# project1.net
KiCad netlist of a schematic drawn in EAGLE
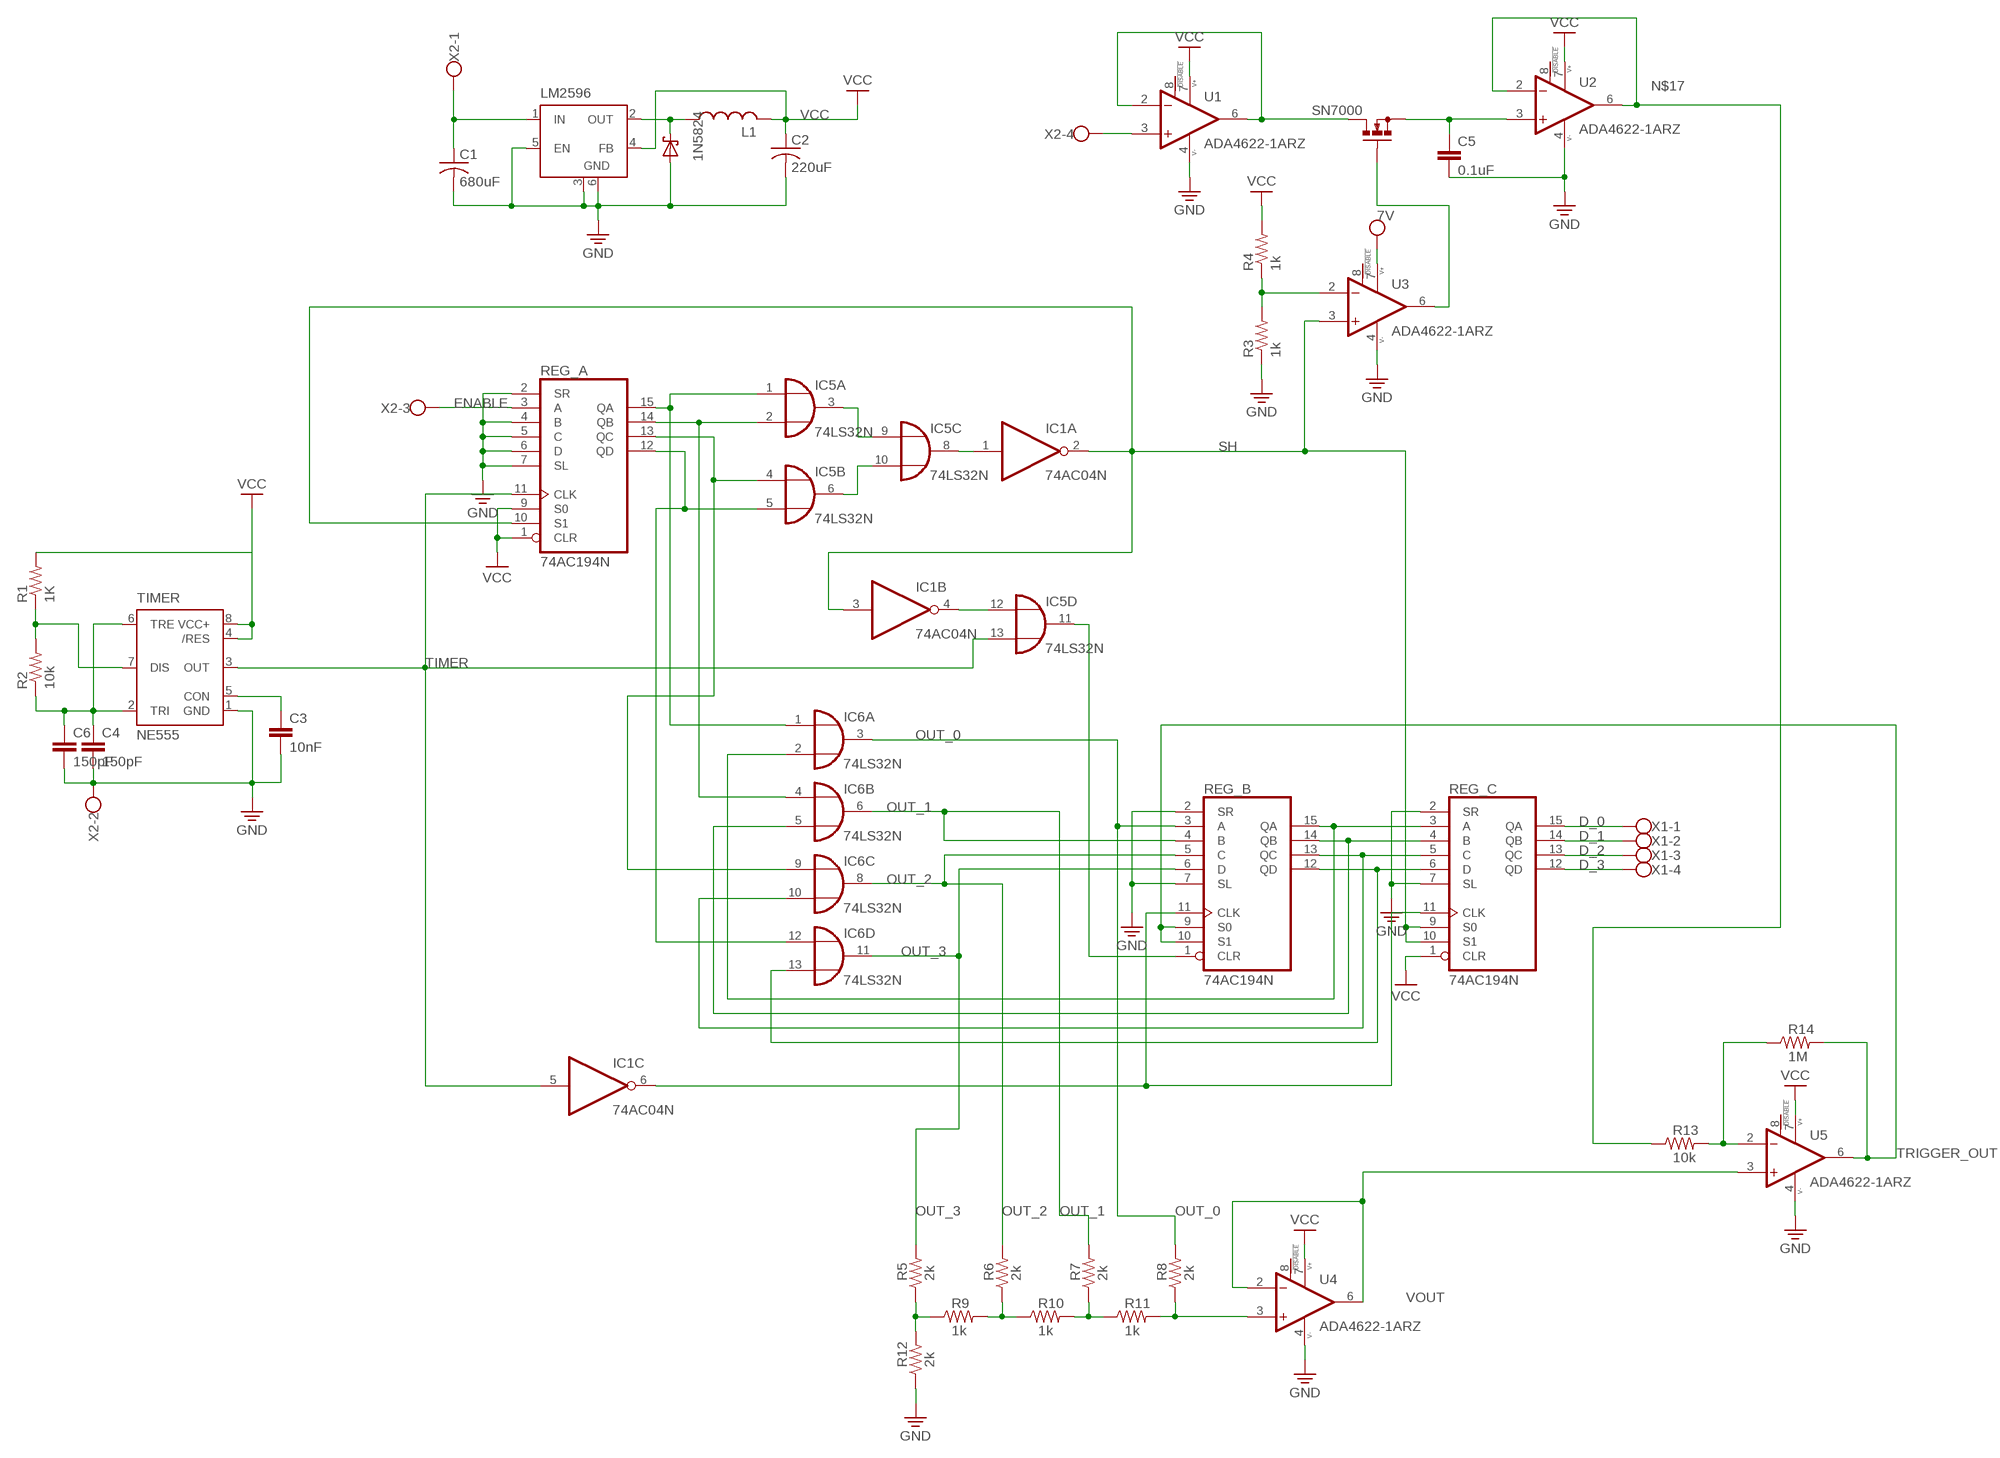
[diagram p0: schematic, sheet 1]

(export (version "E")
  (design (tool "Eeschema 10.0.6"))
  (components
    (comp (ref "1N5824")
      (value "SCHOTTKY-DIODECB417-15")
      (footprint "eagle-import:CB417-15")
      (libsource (lib "eagle-import") (part "SCHOTTKY-DIODECB417-15"))
    )
    (comp (ref "C1")
      (value "680uF")
      (footprint "eagle-import:C025-024X044")
      (libsource (lib "eagle-import") (part "C-US025-024X044"))
    )
    (comp (ref "C2")
      (value "220uF")
      (footprint "eagle-import:C025-024X044")
      (libsource (lib "eagle-import") (part "C-US025-024X044"))
    )
    (comp (ref "C3")
      (value "10nF")
      (footprint "eagle-import:C050-024X044")
      (libsource (lib "eagle-import") (part "C-EU050-024X044"))
    )
    (comp (ref "C4")
      (value "150pF")
      (footprint "eagle-import:C050-024X044")
      (libsource (lib "eagle-import") (part "C-EU050-024X044"))
    )
    (comp (ref "C5")
      (value "0.1uF")
      (footprint "eagle-import:C050-024X044")
      (libsource (lib "eagle-import") (part "C-EU050-024X044"))
    )
    (comp (ref "C6")
      (value "150pF")
      (footprint "eagle-import:C050-024X044")
      (libsource (lib "eagle-import") (part "C-EU050-024X044"))
    )
    (comp (ref "IC1")
      (value "74AC04N")
      (footprint "eagle-import:DIL14")
      (libsource (lib "eagle-import") (part "7404NAC"))
    )
    (comp (ref "IC5")
      (value "74LS32N")
      (footprint "eagle-import:DIL14")
      (libsource (lib "eagle-import") (part "7432NLS"))
    )
    (comp (ref "IC6")
      (value "74LS32N")
      (footprint "eagle-import:DIL14")
      (libsource (lib "eagle-import") (part "7432NLS"))
    )
    (comp (ref "L1")
      (value "L-US0204/7")
      (footprint "eagle-import:0204_7")
      (libsource (lib "eagle-import") (part "L-US0204/7"))
    )
    (comp (ref "LM2596")
      (value "LM2596S")
      (footprint "eagle-import:TO263-5")
      (libsource (lib "eagle-import") (part "LM2596S"))
    )
    (comp (ref "R1")
      (value "1K")
      (footprint "eagle-import:0204_7")
      (libsource (lib "eagle-import") (part "R-US_0204/7"))
    )
    (comp (ref "R2")
      (value "10k")
      (footprint "eagle-import:0204_7")
      (libsource (lib "eagle-import") (part "R-US_0204/7"))
    )
    (comp (ref "R3")
      (value "1k")
      (footprint "eagle-import:0204_7")
      (libsource (lib "eagle-import") (part "R-US_0204/7"))
    )
    (comp (ref "R4")
      (value "1k")
      (footprint "eagle-import:0204_7")
      (libsource (lib "eagle-import") (part "R-US_0204/7"))
    )
    (comp (ref "R5")
      (value "2k")
      (footprint "eagle-import:0204_7")
      (libsource (lib "eagle-import") (part "R-US_0204/7"))
    )
    (comp (ref "R6")
      (value "2k")
      (footprint "eagle-import:0204_7")
      (libsource (lib "eagle-import") (part "R-US_0204/7"))
    )
    (comp (ref "R7")
      (value "2k")
      (footprint "eagle-import:0204_7")
      (libsource (lib "eagle-import") (part "R-US_0204/7"))
    )
    (comp (ref "R8")
      (value "2k")
      (footprint "eagle-import:0204_7")
      (libsource (lib "eagle-import") (part "R-US_0204/7"))
    )
    (comp (ref "R9")
      (value "1k")
      (footprint "eagle-import:0204_7")
      (libsource (lib "eagle-import") (part "R-US_0204/7"))
    )
    (comp (ref "R10")
      (value "1k")
      (footprint "eagle-import:0204_7")
      (libsource (lib "eagle-import") (part "R-US_0204/7"))
    )
    (comp (ref "R11")
      (value "1k")
      (footprint "eagle-import:0204_7")
      (libsource (lib "eagle-import") (part "R-US_0204/7"))
    )
    (comp (ref "R12")
      (value "2k")
      (footprint "eagle-import:0204_7")
      (libsource (lib "eagle-import") (part "R-US_0204/7"))
    )
    (comp (ref "R13")
      (value "10k")
      (footprint "eagle-import:0204_7")
      (libsource (lib "eagle-import") (part "R-US_0204/7"))
    )
    (comp (ref "R14")
      (value "1M")
      (footprint "eagle-import:0204_7")
      (libsource (lib "eagle-import") (part "R-US_0204/7"))
    )
    (comp (ref "REG_A")
      (value "74AC194N")
      (footprint "eagle-import:DIL16")
      (libsource (lib "eagle-import") (part "74194NAC"))
    )
    (comp (ref "REG_B")
      (value "74AC194N")
      (footprint "eagle-import:DIL16")
      (libsource (lib "eagle-import") (part "74194NAC"))
    )
    (comp (ref "REG_C")
      (value "74AC194N")
      (footprint "eagle-import:DIL16")
      (libsource (lib "eagle-import") (part "74194NAC"))
    )
    (comp (ref "SN7000")
      (value "BS170")
      (footprint "eagle-import:SOT54E")
      (libsource (lib "eagle-import") (part "BS170"))
    )
    (comp (ref "TIMER")
      (value "NE555")
      (footprint "eagle-import:DIL-08")
      (fields (field (name "MF") "Arrow Electronics") (field (name "MPN") "NE555N"))
      (libsource (lib "eagle-import") (part "NE555"))
    )
    (comp (ref "U1")
      (value "ADA4622-1ARZ")
      (footprint "eagle-import:SOIC127P600X175-8N")
      (fields (field (name "MF") "Analog Devices"))
      (libsource (lib "eagle-import") (part "ADA4622-1ARZ"))
    )
    (comp (ref "U2")
      (value "ADA4622-1ARZ")
      (footprint "eagle-import:SOIC127P600X175-8N")
      (fields (field (name "MF") "Analog Devices"))
      (libsource (lib "eagle-import") (part "ADA4622-1ARZ"))
    )
    (comp (ref "U3")
      (value "ADA4622-1ARZ")
      (footprint "eagle-import:SOIC127P600X175-8N")
      (fields (field (name "MF") "Analog Devices"))
      (libsource (lib "eagle-import") (part "ADA4622-1ARZ"))
    )
    (comp (ref "U4")
      (value "ADA4622-1ARZ")
      (footprint "eagle-import:SOIC127P600X175-8N")
      (fields (field (name "MF") "Analog Devices"))
      (libsource (lib "eagle-import") (part "ADA4622-1ARZ"))
    )
    (comp (ref "U5")
      (value "ADA4622-1ARZ")
      (footprint "eagle-import:SOIC127P600X175-8N")
      (fields (field (name "MF") "Analog Devices"))
      (libsource (lib "eagle-import") (part "ADA4622-1ARZ"))
    )
    (comp (ref "X1")
      (value "W237-4")
      (footprint "eagle-import:W237-4")
      (libsource (lib "eagle-import") (part "W237-4"))
    )
    (comp (ref "X2")
      (value "W237-4")
      (footprint "eagle-import:W237-4")
      (libsource (lib "eagle-import") (part "W237-4"))
    )
  )
  (nets
    (net (code "1") (name "/D_0") (class "Default")
      (node (ref "REG_C") (pin "15") (pinfunction "QA_15") (pintype "output"))
      (node (ref "X1") (pin "1") (pinfunction "KL_1") (pintype "passive"))
    )
    (net (code "2") (name "/D_1") (class "Default")
      (node (ref "REG_C") (pin "14") (pinfunction "QB_14") (pintype "output"))
      (node (ref "X1") (pin "2") (pinfunction "KL_2") (pintype "passive"))
    )
    (net (code "3") (name "/D_2") (class "Default")
      (node (ref "REG_C") (pin "13") (pinfunction "QC_13") (pintype "output"))
      (node (ref "X1") (pin "3") (pinfunction "KL_3") (pintype "passive"))
    )
    (net (code "4") (name "/D_3") (class "Default")
      (node (ref "REG_C") (pin "12") (pinfunction "QD_12") (pintype "output"))
      (node (ref "X1") (pin "4") (pinfunction "KL_4") (pintype "passive"))
    )
    (net (code "5") (name "/ENABLE") (class "Default")
      (node (ref "REG_A") (pin "3") (pinfunction "A_3") (pintype "input"))
      (node (ref "X2") (pin "3") (pinfunction "KL_3") (pintype "passive"))
    )
    (net (code "6") (name "/N$17") (class "Default")
      (node (ref "R13") (pin "1") (pinfunction "1_1") (pintype "passive"))
      (node (ref "U2") (pin "2") (pinfunction "-IN_2") (pintype "input"))
      (node (ref "U2") (pin "6") (pinfunction "OUT_6") (pintype "output"))
    )
    (net (code "7") (name "/OUT_0") (class "Default")
      (node (ref "IC6") (pin "3") (pinfunction "O_3") (pintype "output"))
      (node (ref "R8") (pin "2") (pinfunction "2_2") (pintype "passive"))
      (node (ref "REG_B") (pin "3") (pinfunction "A_3") (pintype "input"))
    )
    (net (code "8") (name "/OUT_1") (class "Default")
      (node (ref "IC6") (pin "6") (pinfunction "O_6") (pintype "output"))
      (node (ref "R7") (pin "2") (pinfunction "2_2") (pintype "passive"))
      (node (ref "REG_B") (pin "4") (pinfunction "B_4") (pintype "input"))
    )
    (net (code "9") (name "/OUT_2") (class "Default")
      (node (ref "IC6") (pin "8") (pinfunction "O_8") (pintype "output"))
      (node (ref "R6") (pin "2") (pinfunction "2_2") (pintype "passive"))
      (node (ref "REG_B") (pin "5") (pinfunction "C_5") (pintype "input"))
    )
    (net (code "10") (name "/OUT_3") (class "Default")
      (node (ref "IC6") (pin "11") (pinfunction "O_11") (pintype "output"))
      (node (ref "R5") (pin "2") (pinfunction "2_2") (pintype "passive"))
      (node (ref "REG_B") (pin "6") (pinfunction "D_6") (pintype "input"))
    )
    (net (code "11") (name "/SH") (class "Default")
      (node (ref "IC1") (pin "2") (pinfunction "O_2") (pintype "output"))
      (node (ref "IC1") (pin "3") (pinfunction "I_3") (pintype "input"))
      (node (ref "REG_A") (pin "10") (pinfunction "S1_10") (pintype "input"))
      (node (ref "REG_C") (pin "10") (pinfunction "S1_10") (pintype "input"))
      (node (ref "REG_C") (pin "9") (pinfunction "S0_9") (pintype "input"))
      (node (ref "U3") (pin "3") (pinfunction "+IN_3") (pintype "input"))
    )
    (net (code "12") (name "/TIMER") (class "Default")
      (node (ref "IC1") (pin "5") (pinfunction "I_5") (pintype "input"))
      (node (ref "IC5") (pin "13") (pinfunction "I1_13") (pintype "input"))
      (node (ref "REG_A") (pin "11") (pinfunction "CLK_11") (pintype "input"))
      (node (ref "TIMER") (pin "3") (pinfunction "OUT_3") (pintype "output"))
    )
    (net (code "13") (name "/TRIGGER_OUT") (class "Default")
      (node (ref "R14") (pin "2") (pinfunction "2_2") (pintype "passive"))
      (node (ref "REG_B") (pin "10") (pinfunction "S1_10") (pintype "input"))
      (node (ref "REG_B") (pin "9") (pinfunction "S0_9") (pintype "input"))
      (node (ref "U5") (pin "6") (pinfunction "OUT_6") (pintype "output"))
    )
    (net (code "14") (name "/VOUT") (class "Default")
      (node (ref "U4") (pin "2") (pinfunction "-IN_2") (pintype "input"))
      (node (ref "U4") (pin "6") (pinfunction "OUT_6") (pintype "output"))
      (node (ref "U5") (pin "3") (pinfunction "+IN_3") (pintype "input"))
    )
    (net (code "15") (name "7V") (class "Default")
      (node (ref "C2") (pin "1") (pinfunction "1_1") (pintype "passive"))
      (node (ref "L1") (pin "2") (pinfunction "2_2") (pintype "passive"))
      (node (ref "LM2596") (pin "4") (pinfunction "FB_4") (pintype "input"))
      (node (ref "R1") (pin "2") (pinfunction "2_2") (pintype "passive"))
      (node (ref "R4") (pin "2") (pinfunction "2_2") (pintype "passive"))
      (node (ref "REG_A") (pin "1") (pinfunction "CLR_1") (pintype "input"))
      (node (ref "REG_A") (pin "9") (pinfunction "S0_9") (pintype "input"))
      (node (ref "REG_C") (pin "1") (pinfunction "CLR_1") (pintype "input"))
      (node (ref "TIMER") (pin "4") (pinfunction "/RES_4") (pintype "input"))
      (node (ref "TIMER") (pin "8") (pinfunction "VCC+_8") (pintype "power_in"))
      (node (ref "U1") (pin "7") (pinfunction "V+_7") (pintype "power_in"))
      (node (ref "U2") (pin "7") (pinfunction "V+_7") (pintype "power_in"))
      (node (ref "U3") (pin "7") (pinfunction "V+_7") (pintype "power_in"))
      (node (ref "U4") (pin "7") (pinfunction "V+_7") (pintype "power_in"))
      (node (ref "U5") (pin "7") (pinfunction "V+_7") (pintype "power_in"))
    )
    (net (code "16") (name "GND") (class "Default")
      (node (ref "1N5824") (pin "A") (pinfunction "A_A") (pintype "passive"))
      (node (ref "C1") (pin "2") (pinfunction "2_2") (pintype "passive"))
      (node (ref "C2") (pin "2") (pinfunction "2_2") (pintype "passive"))
      (node (ref "C3") (pin "2") (pinfunction "2_2") (pintype "passive"))
      (node (ref "C4") (pin "2") (pinfunction "2_2") (pintype "passive"))
      (node (ref "C5") (pin "2") (pinfunction "2_2") (pintype "passive"))
      (node (ref "C6") (pin "2") (pinfunction "2_2") (pintype "passive"))
      (node (ref "LM2596") (pin "3") (pinfunction "GND_3") (pintype "power_in"))
      (node (ref "LM2596") (pin "5") (pinfunction "EN_5") (pintype "input"))
      (node (ref "LM2596") (pin "6") (pinfunction "GND_6") (pintype "power_in"))
      (node (ref "R12") (pin "1") (pinfunction "1_1") (pintype "passive"))
      (node (ref "R3") (pin "1") (pinfunction "1_1") (pintype "passive"))
      (node (ref "REG_A") (pin "2") (pinfunction "SR_2") (pintype "input"))
      (node (ref "REG_A") (pin "4") (pinfunction "B_4") (pintype "input"))
      (node (ref "REG_A") (pin "5") (pinfunction "C_5") (pintype "input"))
      (node (ref "REG_A") (pin "6") (pinfunction "D_6") (pintype "input"))
      (node (ref "REG_A") (pin "7") (pinfunction "SL_7") (pintype "input"))
      (node (ref "REG_B") (pin "2") (pinfunction "SR_2") (pintype "input"))
      (node (ref "REG_B") (pin "7") (pinfunction "SL_7") (pintype "input"))
      (node (ref "REG_C") (pin "2") (pinfunction "SR_2") (pintype "input"))
      (node (ref "REG_C") (pin "7") (pinfunction "SL_7") (pintype "input"))
      (node (ref "TIMER") (pin "1") (pinfunction "GND_1") (pintype "power_in"))
      (node (ref "U1") (pin "4") (pinfunction "V-_4") (pintype "power_in"))
      (node (ref "U2") (pin "4") (pinfunction "V-_4") (pintype "power_in"))
      (node (ref "U3") (pin "4") (pinfunction "V-_4") (pintype "power_in"))
      (node (ref "U4") (pin "4") (pinfunction "V-_4") (pintype "power_in"))
      (node (ref "U5") (pin "4") (pinfunction "V-_4") (pintype "power_in"))
      (node (ref "X2") (pin "2") (pinfunction "KL_2") (pintype "passive"))
    )
    (net (code "17") (name "Net-(IC1A-I)") (class "Default")
      (node (ref "IC1") (pin "1") (pinfunction "I_1") (pintype "input"))
      (node (ref "IC5") (pin "8") (pinfunction "O_8") (pintype "output"))
    )
    (net (code "18") (name "Net-(IC1B-O)") (class "Default")
      (node (ref "IC1") (pin "4") (pinfunction "O_4") (pintype "output"))
      (node (ref "IC5") (pin "12") (pinfunction "I0_12") (pintype "input"))
    )
    (net (code "19") (name "Net-(IC1C-O)") (class "Default")
      (node (ref "IC1") (pin "6") (pinfunction "O_6") (pintype "output"))
      (node (ref "REG_B") (pin "11") (pinfunction "CLK_11") (pintype "input"))
      (node (ref "REG_C") (pin "11") (pinfunction "CLK_11") (pintype "input"))
    )
    (net (code "20") (name "Net-(IC5A-I0)") (class "Default")
      (node (ref "IC5") (pin "1") (pinfunction "I0_1") (pintype "input"))
      (node (ref "IC6") (pin "1") (pinfunction "I0_1") (pintype "input"))
      (node (ref "REG_A") (pin "15") (pinfunction "QA_15") (pintype "output"))
    )
    (net (code "21") (name "Net-(IC5A-I1)") (class "Default")
      (node (ref "IC5") (pin "2") (pinfunction "I1_2") (pintype "input"))
      (node (ref "IC6") (pin "4") (pinfunction "I0_4") (pintype "input"))
      (node (ref "REG_A") (pin "14") (pinfunction "QB_14") (pintype "output"))
    )
    (net (code "22") (name "Net-(IC5A-O)") (class "Default")
      (node (ref "IC5") (pin "3") (pinfunction "O_3") (pintype "output"))
      (node (ref "IC5") (pin "9") (pinfunction "I0_9") (pintype "input"))
    )
    (net (code "23") (name "Net-(IC5B-I0)") (class "Default")
      (node (ref "IC5") (pin "4") (pinfunction "I0_4") (pintype "input"))
      (node (ref "IC6") (pin "9") (pinfunction "I0_9") (pintype "input"))
      (node (ref "REG_A") (pin "13") (pinfunction "QC_13") (pintype "output"))
    )
    (net (code "24") (name "Net-(IC5B-I1)") (class "Default")
      (node (ref "IC5") (pin "5") (pinfunction "I1_5") (pintype "input"))
      (node (ref "IC6") (pin "12") (pinfunction "I0_12") (pintype "input"))
      (node (ref "REG_A") (pin "12") (pinfunction "QD_12") (pintype "output"))
    )
    (net (code "25") (name "Net-(IC5B-O)") (class "Default")
      (node (ref "IC5") (pin "10") (pinfunction "I1_10") (pintype "input"))
      (node (ref "IC5") (pin "6") (pinfunction "O_6") (pintype "output"))
    )
    (net (code "26") (name "Net-(IC5D-O)") (class "Default")
      (node (ref "IC5") (pin "11") (pinfunction "O_11") (pintype "output"))
      (node (ref "REG_B") (pin "1") (pinfunction "CLR_1") (pintype "input"))
    )
    (net (code "27") (name "Net-(IC6A-I1)") (class "Default")
      (node (ref "IC6") (pin "2") (pinfunction "I1_2") (pintype "input"))
      (node (ref "REG_B") (pin "15") (pinfunction "QA_15") (pintype "output"))
      (node (ref "REG_C") (pin "3") (pinfunction "A_3") (pintype "input"))
    )
    (net (code "28") (name "Net-(IC6B-I1)") (class "Default")
      (node (ref "IC6") (pin "5") (pinfunction "I1_5") (pintype "input"))
      (node (ref "REG_B") (pin "14") (pinfunction "QB_14") (pintype "output"))
      (node (ref "REG_C") (pin "4") (pinfunction "B_4") (pintype "input"))
    )
    (net (code "29") (name "Net-(IC6C-I1)") (class "Default")
      (node (ref "IC6") (pin "10") (pinfunction "I1_10") (pintype "input"))
      (node (ref "REG_B") (pin "13") (pinfunction "QC_13") (pintype "output"))
      (node (ref "REG_C") (pin "5") (pinfunction "C_5") (pintype "input"))
    )
    (net (code "30") (name "Net-(IC6D-I1)") (class "Default")
      (node (ref "IC6") (pin "13") (pinfunction "I1_13") (pintype "input"))
      (node (ref "REG_B") (pin "12") (pinfunction "QD_12") (pintype "output"))
      (node (ref "REG_C") (pin "6") (pinfunction "D_6") (pintype "input"))
    )
    (net (code "31") (name "Net-(LM2596-IN)") (class "Default")
      (node (ref "C1") (pin "1") (pinfunction "1_1") (pintype "passive"))
      (node (ref "LM2596") (pin "1") (pinfunction "IN_1") (pintype "input"))
      (node (ref "X2") (pin "1") (pinfunction "KL_1") (pintype "passive"))
    )
    (net (code "32") (name "Net-(LM2596-OUT)") (class "Default")
      (node (ref "1N5824") (pin "C") (pinfunction "C_C") (pintype "passive"))
      (node (ref "L1") (pin "1") (pinfunction "1_1") (pintype "passive"))
      (node (ref "LM2596") (pin "2") (pinfunction "OUT_2") (pintype "output"))
    )
    (net (code "33") (name "Net-(R10-Pad1)") (class "Default")
      (node (ref "R10") (pin "1") (pinfunction "1_1") (pintype "passive"))
      (node (ref "R6") (pin "1") (pinfunction "1_1") (pintype "passive"))
      (node (ref "R9") (pin "2") (pinfunction "2_2") (pintype "passive"))
    )
    (net (code "34") (name "Net-(R10-Pad2)") (class "Default")
      (node (ref "R10") (pin "2") (pinfunction "2_2") (pintype "passive"))
      (node (ref "R11") (pin "1") (pinfunction "1_1") (pintype "passive"))
      (node (ref "R7") (pin "1") (pinfunction "1_1") (pintype "passive"))
    )
    (net (code "35") (name "Net-(R12-Pad2)") (class "Default")
      (node (ref "R12") (pin "2") (pinfunction "2_2") (pintype "passive"))
      (node (ref "R5") (pin "1") (pinfunction "1_1") (pintype "passive"))
      (node (ref "R9") (pin "1") (pinfunction "1_1") (pintype "passive"))
    )
    (net (code "36") (name "Net-(TIMER-CON)") (class "Default")
      (node (ref "C3") (pin "1") (pinfunction "1_1") (pintype "passive"))
      (node (ref "TIMER") (pin "5") (pinfunction "CON_5") (pintype "input"))
    )
    (net (code "37") (name "Net-(TIMER-DIS)") (class "Default")
      (node (ref "R1") (pin "1") (pinfunction "1_1") (pintype "passive"))
      (node (ref "R2") (pin "2") (pinfunction "2_2") (pintype "passive"))
      (node (ref "TIMER") (pin "7") (pinfunction "DIS_7") (pintype "input"))
    )
    (net (code "38") (name "Net-(TIMER-TRE)") (class "Default")
      (node (ref "C4") (pin "1") (pinfunction "1_1") (pintype "passive"))
      (node (ref "C6") (pin "1") (pinfunction "1_1") (pintype "passive"))
      (node (ref "R2") (pin "1") (pinfunction "1_1") (pintype "passive"))
      (node (ref "TIMER") (pin "2") (pinfunction "TRI_2") (pintype "input"))
      (node (ref "TIMER") (pin "6") (pinfunction "TRE_6") (pintype "input"))
    )
    (net (code "39") (name "Net-(U1-+IN)") (class "Default")
      (node (ref "U1") (pin "3") (pinfunction "+IN_3") (pintype "input"))
      (node (ref "X2") (pin "4") (pinfunction "KL_4") (pintype "passive"))
    )
    (net (code "40") (name "Net-(U1--IN)") (class "Default")
      (node (ref "SN7000") (pin "D") (pinfunction "D_D") (pintype "passive"))
      (node (ref "U1") (pin "2") (pinfunction "-IN_2") (pintype "input"))
      (node (ref "U1") (pin "6") (pinfunction "OUT_6") (pintype "output"))
    )
    (net (code "41") (name "Net-(U2-+IN)") (class "Default")
      (node (ref "C5") (pin "1") (pinfunction "1_1") (pintype "passive"))
      (node (ref "SN7000") (pin "S") (pinfunction "S_S") (pintype "passive"))
      (node (ref "U2") (pin "3") (pinfunction "+IN_3") (pintype "input"))
    )
    (net (code "42") (name "Net-(U3--IN)") (class "Default")
      (node (ref "R3") (pin "2") (pinfunction "2_2") (pintype "passive"))
      (node (ref "R4") (pin "1") (pinfunction "1_1") (pintype "passive"))
      (node (ref "U3") (pin "2") (pinfunction "-IN_2") (pintype "input"))
    )
    (net (code "43") (name "Net-(U3-OUT)") (class "Default")
      (node (ref "SN7000") (pin "G") (pinfunction "G_G") (pintype "passive"))
      (node (ref "U3") (pin "6") (pinfunction "OUT_6") (pintype "output"))
    )
    (net (code "44") (name "Net-(U4-+IN)") (class "Default")
      (node (ref "R11") (pin "2") (pinfunction "2_2") (pintype "passive"))
      (node (ref "R8") (pin "1") (pinfunction "1_1") (pintype "passive"))
      (node (ref "U4") (pin "3") (pinfunction "+IN_3") (pintype "input"))
    )
    (net (code "45") (name "Net-(U5--IN)") (class "Default")
      (node (ref "R13") (pin "2") (pinfunction "2_2") (pintype "passive"))
      (node (ref "R14") (pin "1") (pinfunction "1_1") (pintype "passive"))
      (node (ref "U5") (pin "2") (pinfunction "-IN_2") (pintype "input"))
    )
    (net (code "46") (name "unconnected-(U1-~{DISABLE}-Pad8)") (class "Default")
      (node (ref "U1") (pin "8") (pinfunction "~{DISABLE}_8") (pintype "input"))
    )
    (net (code "47") (name "unconnected-(U2-~{DISABLE}-Pad8)") (class "Default")
      (node (ref "U2") (pin "8") (pinfunction "~{DISABLE}_8") (pintype "input"))
    )
    (net (code "48") (name "unconnected-(U3-~{DISABLE}-Pad8)") (class "Default")
      (node (ref "U3") (pin "8") (pinfunction "~{DISABLE}_8") (pintype "input"))
    )
    (net (code "49") (name "unconnected-(U4-~{DISABLE}-Pad8)") (class "Default")
      (node (ref "U4") (pin "8") (pinfunction "~{DISABLE}_8") (pintype "input"))
    )
    (net (code "50") (name "unconnected-(U5-~{DISABLE}-Pad8)") (class "Default")
      (node (ref "U5") (pin "8") (pinfunction "~{DISABLE}_8") (pintype "input"))
    )
  )
)
